# SCH_Plantcare_Module-v3_2024-10-22.net
KiCad netlist of a schematic drawn in EasyEDA
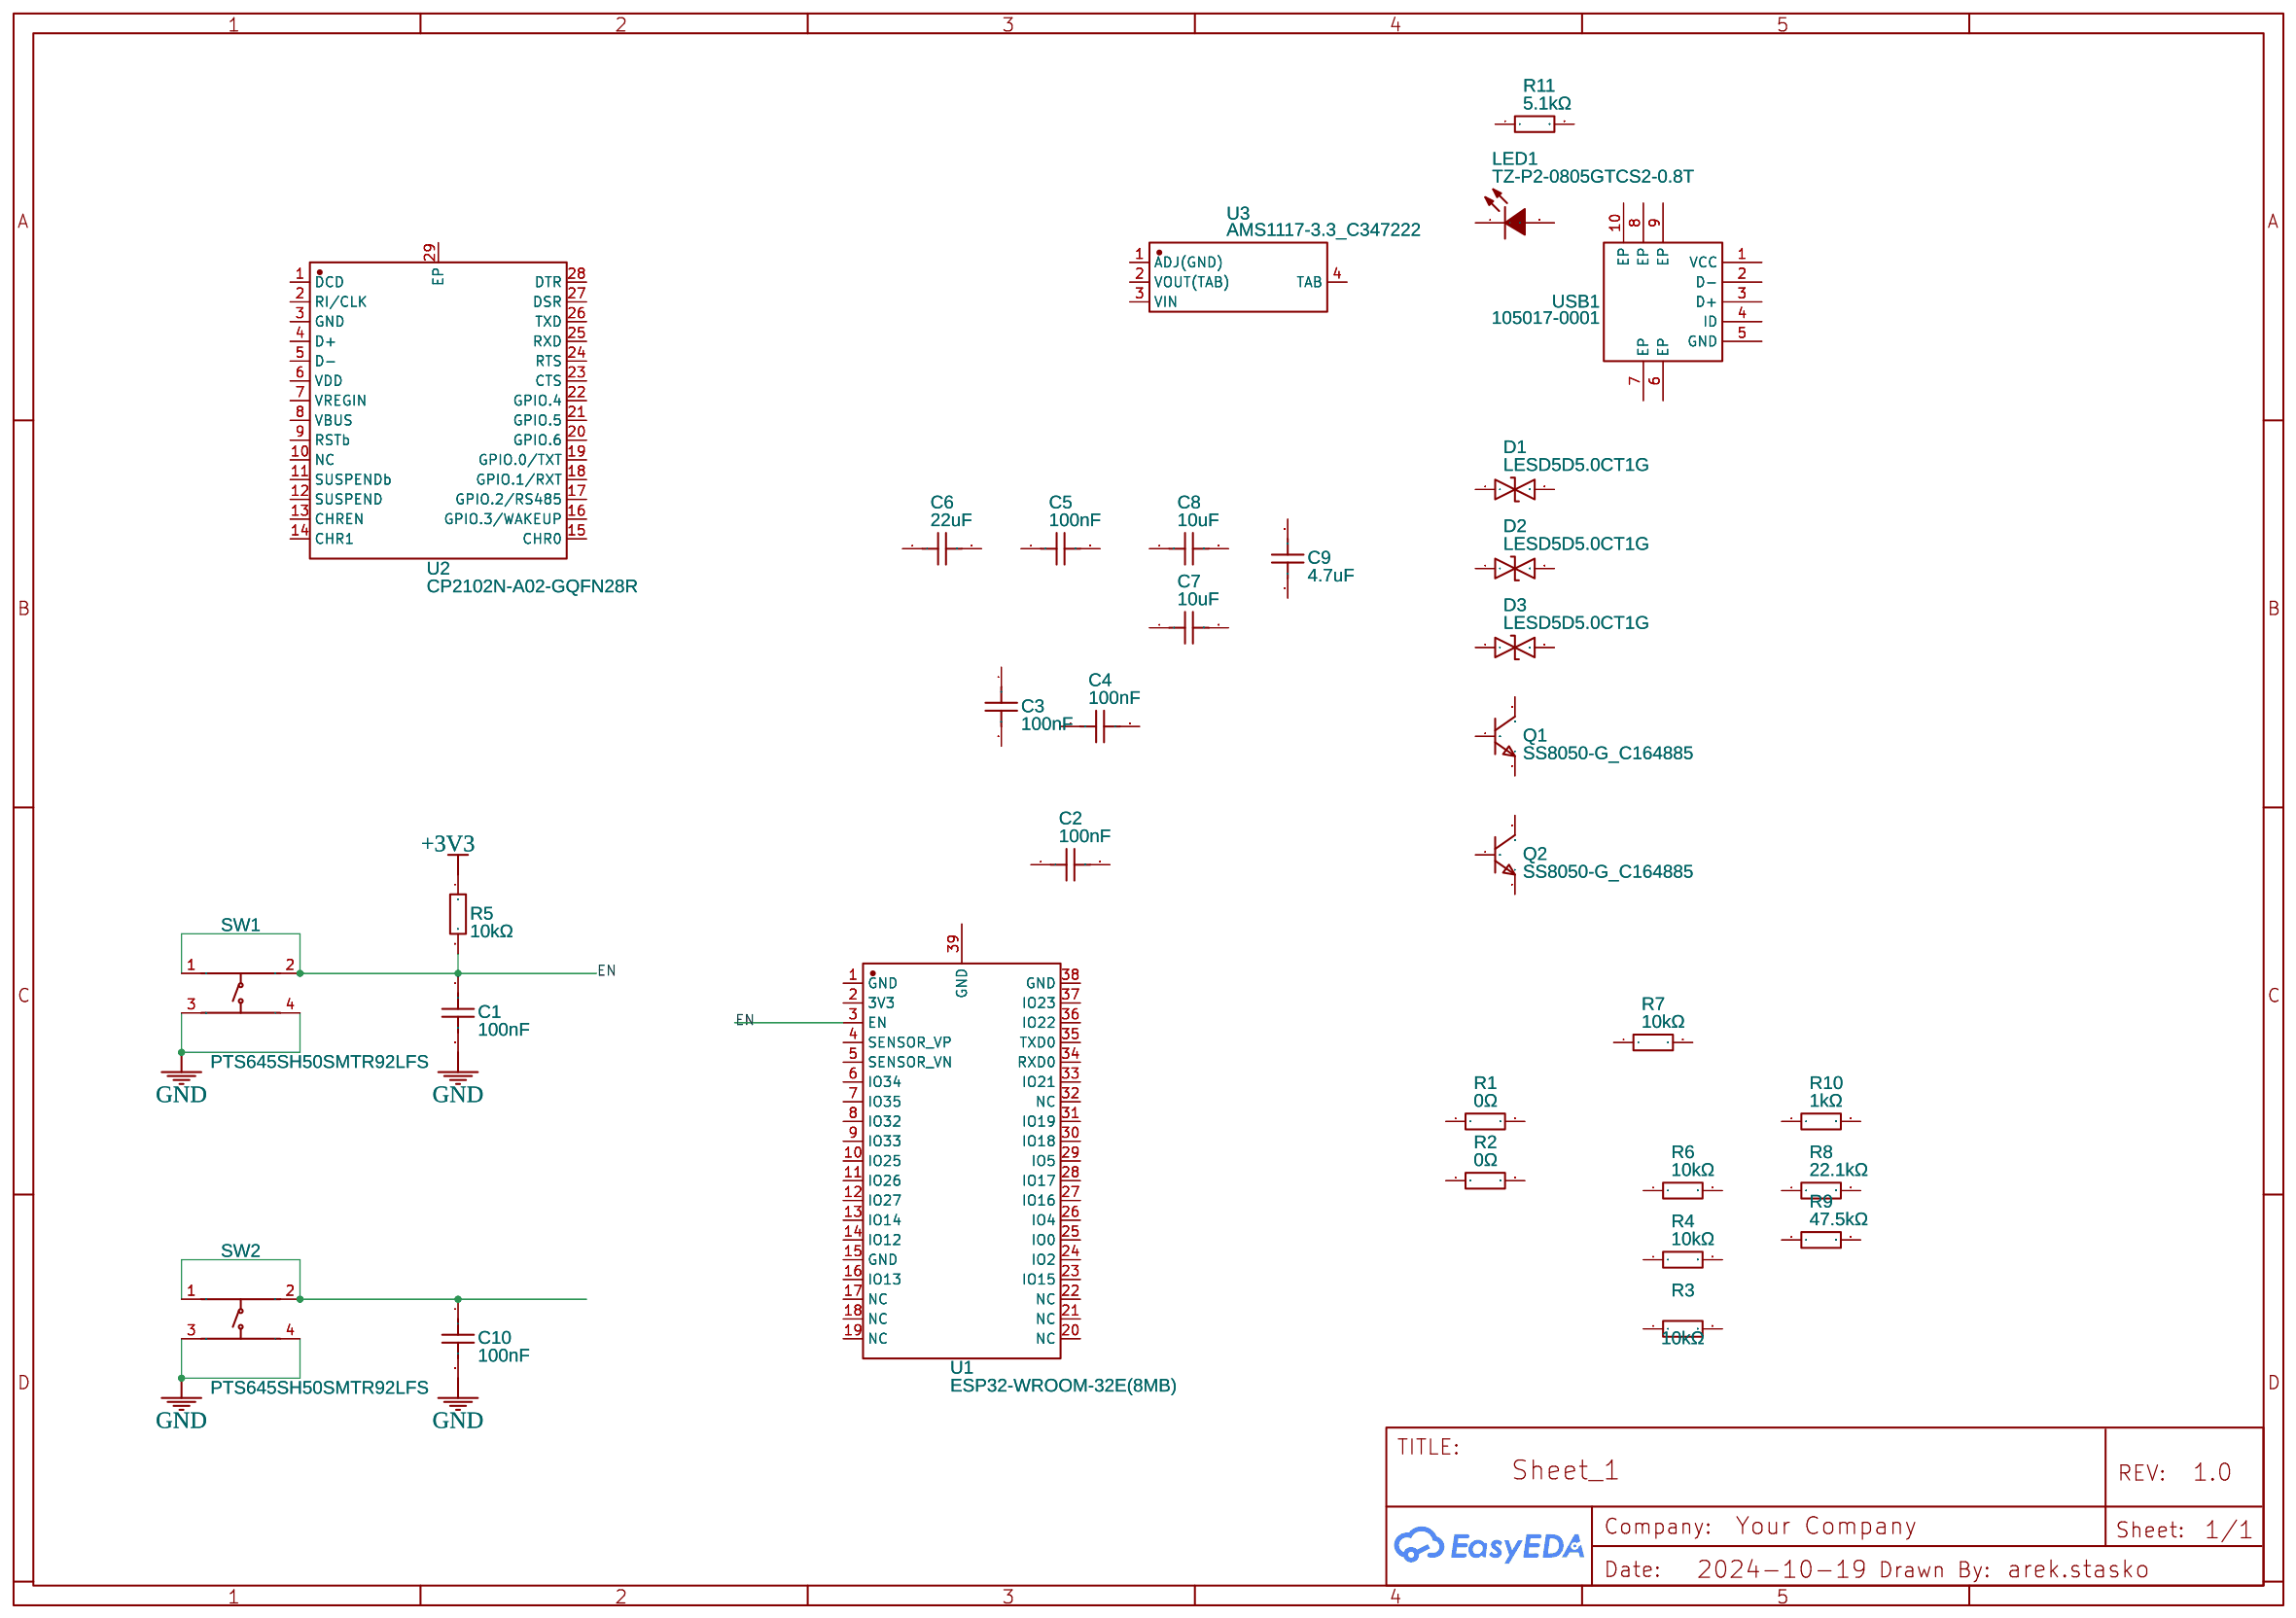
[diagram p0: schematic sheet]

(export (version "E")
  (design (tool "Eeschema 10.0.6"))
  (components
    (comp (ref "C1")
      (value "100nF")
      (fields
        (field (name "Manufacturer Part") "CL05B104KO5NNNC")
        (field (name "Manufacturer") "SAMSUNG(三星)")
      )
      (libsource (lib "") (part "CL05B104KO5NNNC_1"))
    )
    (comp (ref "C2")
      (value "100nF")
      (fields
        (field (name "Manufacturer Part") "CL05B104KO5NNNC")
        (field (name "Manufacturer") "SAMSUNG(三星)")
      )
      (libsource (lib "") (part "CL05B104KO5NNNC"))
    )
    (comp (ref "C3")
      (value "100nF")
      (fields
        (field (name "Manufacturer Part") "CL05B104KO5NNNC")
        (field (name "Manufacturer") "SAMSUNG(三星)")
      )
      (libsource (lib "") (part "CL05B104KO5NNNC_1"))
    )
    (comp (ref "C4")
      (value "100nF")
      (fields
        (field (name "Manufacturer Part") "CL05B104KO5NNNC")
        (field (name "Manufacturer") "SAMSUNG(三星)")
      )
      (libsource (lib "") (part "CL05B104KO5NNNC"))
    )
    (comp (ref "C5")
      (value "100nF")
      (fields
        (field (name "Manufacturer Part") "CL05B104KO5NNNC")
        (field (name "Manufacturer") "SAMSUNG(三星)")
      )
      (libsource (lib "") (part "CL05B104KO5NNNC"))
    )
    (comp (ref "C6")
      (value "22uF")
      (fields
        (field (name "Manufacturer Part") "CL21A226MAYNNNE")
        (field (name "Manufacturer") "SAMSUNG(三星)")
      )
      (libsource (lib "") (part "CL21A226MAYNNNE"))
    )
    (comp (ref "C7")
      (value "10uF")
      (fields
        (field (name "Manufacturer Part") "CL05A106MP5NUNC")
        (field (name "Manufacturer") "SAMSUNG(三星)")
      )
      (libsource (lib "") (part "CL05A106MP5NUNC_C315248"))
    )
    (comp (ref "C8")
      (value "10uF")
      (fields
        (field (name "Manufacturer Part") "CL05A106MP5NUNC")
        (field (name "Manufacturer") "SAMSUNG(三星)")
      )
      (libsource (lib "") (part "CL05A106MP5NUNC_C315248"))
    )
    (comp (ref "C9")
      (value "4.7uF")
      (fields
        (field (name "Manufacturer Part") "CL05A475KP5NRNC")
        (field (name "Manufacturer") "SAMSUNG(三星)")
      )
      (libsource (lib "") (part "CL05A475KP5NRNC"))
    )
    (comp (ref "C10")
      (value "100nF")
      (fields
        (field (name "Manufacturer Part") "CL05B104KO5NNNC")
        (field (name "Manufacturer") "SAMSUNG(三星)")
      )
      (libsource (lib "") (part "CL05B104KO5NNNC_1"))
    )
    (comp (ref "D1")
      (value "LESD5D5.0CT1G")
      (fields (field (name "Manufacturer") "LRC(乐山无线电)"))
      (libsource (lib "") (part "LESD5D5.0CT1G"))
    )
    (comp (ref "D2")
      (value "LESD5D5.0CT1G")
      (fields (field (name "Manufacturer") "LRC(乐山无线电)"))
      (libsource (lib "") (part "LESD5D5.0CT1G"))
    )
    (comp (ref "D3")
      (value "LESD5D5.0CT1G")
      (fields (field (name "Manufacturer") "LRC(乐山无线电)"))
      (libsource (lib "") (part "LESD5D5.0CT1G"))
    )
    (comp (ref "LED1")
      (value "TZ-P2-0805GTCS2-0.8T")
      (fields (field (name "Manufacturer") "TUOZHAN(拓展光电)"))
      (libsource (lib "") (part "TZ-P2-0805GTCS2-0.8T"))
    )
    (comp (ref "Q1")
      (value "SS8050-G_C164885")
      (fields (field (name "Manufacturer Part") "SS8050-G") (field (name "Manufacturer") "CJ(江苏长电/长晶)"))
      (libsource (lib "") (part "SS8050-G_C164885"))
    )
    (comp (ref "Q2")
      (value "SS8050-G_C164885")
      (fields (field (name "Manufacturer Part") "SS8050-G") (field (name "Manufacturer") "CJ(江苏长电/长晶)"))
      (libsource (lib "") (part "SS8050-G_C164885"))
    )
    (comp (ref "R1")
      (value "0Ω")
      (fields
        (field (name "Manufacturer Part") "0402WGF0000TCE")
        (field (name "Manufacturer") "UNI-ROYAL(厚声)")
      )
      (libsource (lib "") (part "0402WGF0000TCE"))
    )
    (comp (ref "R2")
      (value "0Ω")
      (fields
        (field (name "Manufacturer Part") "0402WGF0000TCE")
        (field (name "Manufacturer") "UNI-ROYAL(厚声)")
      )
      (libsource (lib "") (part "0402WGF0000TCE"))
    )
    (comp (ref "R3")
      (value "10kΩ")
      (fields
        (field (name "Manufacturer Part") "0402WGF1002TCE")
        (field (name "Manufacturer") "UNI-ROYAL(厚声)")
      )
      (libsource (lib "") (part "0402WGF1002TCE"))
    )
    (comp (ref "R4")
      (value "10kΩ")
      (fields
        (field (name "Manufacturer Part") "0402WGF1002TCE")
        (field (name "Manufacturer") "UNI-ROYAL(厚声)")
      )
      (libsource (lib "") (part "0402WGF1002TCE"))
    )
    (comp (ref "R5")
      (value "10kΩ")
      (fields
        (field (name "Manufacturer Part") "0402WGF1002TCE")
        (field (name "Manufacturer") "UNI-ROYAL(厚声)")
      )
      (libsource (lib "") (part "0402WGF1002TCE_1"))
    )
    (comp (ref "R6")
      (value "10kΩ")
      (fields
        (field (name "Manufacturer Part") "0402WGF1002TCE")
        (field (name "Manufacturer") "UNI-ROYAL(厚声)")
      )
      (libsource (lib "") (part "0402WGF1002TCE"))
    )
    (comp (ref "R7")
      (value "10kΩ")
      (fields
        (field (name "Manufacturer Part") "0402WGF1002TCE")
        (field (name "Manufacturer") "UNI-ROYAL(厚声)")
      )
      (libsource (lib "") (part "0402WGF1002TCE"))
    )
    (comp (ref "R8")
      (value "22.1kΩ")
      (fields
        (field (name "Manufacturer Part") "0402WGF2212TCE")
        (field (name "Manufacturer") "UNI-ROYAL(厚声)")
      )
      (libsource (lib "") (part "0402WGF2212TCE"))
    )
    (comp (ref "R9")
      (value "47.5kΩ")
      (fields
        (field (name "Manufacturer Part") "0402WGF4752TCE")
        (field (name "Manufacturer") "UNI-ROYAL(厚声)")
      )
      (libsource (lib "") (part "0402WGF4752TCE"))
    )
    (comp (ref "R10")
      (value "1kΩ")
      (fields
        (field (name "Manufacturer Part") "0402WGF1001TCE")
        (field (name "Manufacturer") "UNI-ROYAL(厚声)")
      )
      (libsource (lib "") (part "0402WGF1001TCE"))
    )
    (comp (ref "R11")
      (value "5.1kΩ")
      (fields
        (field (name "Manufacturer Part") "0402WGF5101TCE")
        (field (name "Manufacturer") "UNI-ROYAL(厚声)")
      )
      (libsource (lib "") (part "0402WGF5101TCE"))
    )
    (comp (ref "SW1")
      (value "PTS645SH50SMTR92LFS")
      (fields (field (name "Manufacturer") "C&K"))
      (libsource (lib "") (part "PTS645SH50SMTR92LFS"))
    )
    (comp (ref "SW2")
      (value "PTS645SH50SMTR92LFS")
      (fields (field (name "Manufacturer") "C&K"))
      (libsource (lib "") (part "PTS645SH50SMTR92LFS"))
    )
    (comp (ref "U1")
      (value "ESP32-WROOM-32E(8MB)")
      (fields
        (field (name "Manufacturer Part") "ESP32-WROOM-32E-N8")
        (field (name "Manufacturer") "ESPRESSIF(乐鑫)")
      )
      (libsource (lib "") (part "ESP32-WROOM-32E(8MB)"))
    )
    (comp (ref "U2")
      (value "CP2102N-A02-GQFN28R")
      (fields (field (name "Manufacturer") "SKYWORKS/SILICON LABS(芯科)"))
      (libsource (lib "") (part "CP2102N-A02-GQFN28R"))
    )
    (comp (ref "U3")
      (value "AMS1117-3.3_C347222")
      (fields (field (name "Manufacturer Part") "AMS1117-3.3") (field (name "Manufacturer") "UMW(友台半导体)"))
      (libsource (lib "") (part "AMS1117-3.3_C347222"))
    )
    (comp (ref "USB1")
      (value "105017-0001")
      (fields (field (name "Manufacturer Part") "1050170001") (field (name "Manufacturer") "MOLEX"))
      (libsource (lib "") (part "105017-0001"))
    )
  )
  (nets
    (net (code "1") (name "+3V3") (class "Default")
      (node (ref "R5") (pin "1") (pinfunction "1_1") (pintype "input"))
    )
    (net (code "2") (name "/EN") (class "Default")
      (node (ref "C1") (pin "1") (pinfunction "1_1") (pintype "unspecified"))
      (node (ref "R5") (pin "2") (pinfunction "2_2") (pintype "input"))
      (node (ref "SW1") (pin "1") (pinfunction "1_1") (pintype "unspecified"))
      (node (ref "SW1") (pin "2") (pinfunction "2_2") (pintype "unspecified"))
      (node (ref "U1") (pin "3") (pinfunction "EN_3") (pintype "unspecified"))
    )
    (net (code "3") (name "GND") (class "Default")
      (node (ref "C1") (pin "2") (pinfunction "2_2") (pintype "unspecified"))
      (node (ref "C10") (pin "2") (pinfunction "2_2") (pintype "unspecified"))
      (node (ref "SW1") (pin "3") (pinfunction "3_3") (pintype "unspecified"))
      (node (ref "SW1") (pin "4") (pinfunction "4_4") (pintype "unspecified"))
      (node (ref "SW2") (pin "3") (pinfunction "3_3") (pintype "unspecified"))
      (node (ref "SW2") (pin "4") (pinfunction "4_4") (pintype "unspecified"))
    )
    (net (code "4") (name "Net-(C10-Pad1)") (class "Default")
      (node (ref "C10") (pin "1") (pinfunction "1_1") (pintype "unspecified"))
      (node (ref "SW2") (pin "1") (pinfunction "1_1") (pintype "unspecified"))
      (node (ref "SW2") (pin "2") (pinfunction "2_2") (pintype "unspecified"))
    )
    (net (code "5") (name "unconnected-(C2-Pad1)") (class "Default")
      (node (ref "C2") (pin "1") (pinfunction "1_1") (pintype "unspecified"))
    )
    (net (code "6") (name "unconnected-(C2-Pad2)") (class "Default")
      (node (ref "C2") (pin "2") (pinfunction "2_2") (pintype "unspecified"))
    )
    (net (code "7") (name "unconnected-(C3-Pad1)") (class "Default")
      (node (ref "C3") (pin "1") (pinfunction "1_1") (pintype "unspecified"))
    )
    (net (code "8") (name "unconnected-(C3-Pad2)") (class "Default")
      (node (ref "C3") (pin "2") (pinfunction "2_2") (pintype "unspecified"))
    )
    (net (code "9") (name "unconnected-(C4-Pad1)") (class "Default")
      (node (ref "C4") (pin "1") (pinfunction "1_1") (pintype "unspecified"))
    )
    (net (code "10") (name "unconnected-(C4-Pad2)") (class "Default")
      (node (ref "C4") (pin "2") (pinfunction "2_2") (pintype "unspecified"))
    )
    (net (code "11") (name "unconnected-(C5-Pad1)") (class "Default")
      (node (ref "C5") (pin "1") (pinfunction "1_1") (pintype "unspecified"))
    )
    (net (code "12") (name "unconnected-(C5-Pad2)") (class "Default")
      (node (ref "C5") (pin "2") (pinfunction "2_2") (pintype "unspecified"))
    )
    (net (code "13") (name "unconnected-(C6-Pad1)") (class "Default")
      (node (ref "C6") (pin "1") (pinfunction "1_1") (pintype "unspecified"))
    )
    (net (code "14") (name "unconnected-(C6-Pad2)") (class "Default")
      (node (ref "C6") (pin "2") (pinfunction "2_2") (pintype "unspecified"))
    )
    (net (code "15") (name "unconnected-(C7-Pad1)") (class "Default")
      (node (ref "C7") (pin "1") (pinfunction "1_1") (pintype "unspecified"))
    )
    (net (code "16") (name "unconnected-(C7-Pad2)") (class "Default")
      (node (ref "C7") (pin "2") (pinfunction "2_2") (pintype "unspecified"))
    )
    (net (code "17") (name "unconnected-(C8-Pad1)") (class "Default")
      (node (ref "C8") (pin "1") (pinfunction "1_1") (pintype "unspecified"))
    )
    (net (code "18") (name "unconnected-(C8-Pad2)") (class "Default")
      (node (ref "C8") (pin "2") (pinfunction "2_2") (pintype "unspecified"))
    )
    (net (code "19") (name "unconnected-(C9-Pad1)") (class "Default")
      (node (ref "C9") (pin "1") (pinfunction "1_1") (pintype "unspecified"))
    )
    (net (code "20") (name "unconnected-(C9-Pad2)") (class "Default")
      (node (ref "C9") (pin "2") (pinfunction "2_2") (pintype "unspecified"))
    )
    (net (code "21") (name "unconnected-(D1-Pad1)") (class "Default")
      (node (ref "D1") (pin "1") (pinfunction "1_1") (pintype "unspecified"))
    )
    (net (code "22") (name "unconnected-(D1-Pad2)") (class "Default")
      (node (ref "D1") (pin "2") (pinfunction "2_2") (pintype "unspecified"))
    )
    (net (code "23") (name "unconnected-(D2-Pad1)") (class "Default")
      (node (ref "D2") (pin "1") (pinfunction "1_1") (pintype "unspecified"))
    )
    (net (code "24") (name "unconnected-(D2-Pad2)") (class "Default")
      (node (ref "D2") (pin "2") (pinfunction "2_2") (pintype "unspecified"))
    )
    (net (code "25") (name "unconnected-(D3-Pad1)") (class "Default")
      (node (ref "D3") (pin "1") (pinfunction "1_1") (pintype "unspecified"))
    )
    (net (code "26") (name "unconnected-(D3-Pad2)") (class "Default")
      (node (ref "D3") (pin "2") (pinfunction "2_2") (pintype "unspecified"))
    )
    (net (code "27") (name "unconnected-(LED1-+-Pad2)") (class "Default")
      (node (ref "LED1") (pin "2") (pinfunction "+_2") (pintype "unspecified"))
    )
    (net (code "28") (name "unconnected-(LED1---Pad1)") (class "Default")
      (node (ref "LED1") (pin "1") (pinfunction "-_1") (pintype "unspecified"))
    )
    (net (code "29") (name "unconnected-(Q1-B-Pad1)") (class "Default")
      (node (ref "Q1") (pin "1") (pinfunction "B_1") (pintype "unspecified"))
    )
    (net (code "30") (name "unconnected-(Q1-C-Pad3)") (class "Default")
      (node (ref "Q1") (pin "3") (pinfunction "C_3") (pintype "unspecified"))
    )
    (net (code "31") (name "unconnected-(Q1-E-Pad2)") (class "Default")
      (node (ref "Q1") (pin "2") (pinfunction "E_2") (pintype "unspecified"))
    )
    (net (code "32") (name "unconnected-(Q2-B-Pad1)") (class "Default")
      (node (ref "Q2") (pin "1") (pinfunction "B_1") (pintype "unspecified"))
    )
    (net (code "33") (name "unconnected-(Q2-C-Pad3)") (class "Default")
      (node (ref "Q2") (pin "3") (pinfunction "C_3") (pintype "unspecified"))
    )
    (net (code "34") (name "unconnected-(Q2-E-Pad2)") (class "Default")
      (node (ref "Q2") (pin "2") (pinfunction "E_2") (pintype "unspecified"))
    )
    (net (code "35") (name "unconnected-(R1-Pad1)") (class "Default")
      (node (ref "R1") (pin "1") (pinfunction "1_1") (pintype "input"))
    )
    (net (code "36") (name "unconnected-(R1-Pad2)") (class "Default")
      (node (ref "R1") (pin "2") (pinfunction "2_2") (pintype "input"))
    )
    (net (code "37") (name "unconnected-(R2-Pad1)") (class "Default")
      (node (ref "R2") (pin "1") (pinfunction "1_1") (pintype "input"))
    )
    (net (code "38") (name "unconnected-(R2-Pad2)") (class "Default")
      (node (ref "R2") (pin "2") (pinfunction "2_2") (pintype "input"))
    )
    (net (code "39") (name "unconnected-(R3-Pad1)") (class "Default")
      (node (ref "R3") (pin "1") (pinfunction "1_1") (pintype "input"))
    )
    (net (code "40") (name "unconnected-(R3-Pad2)") (class "Default")
      (node (ref "R3") (pin "2") (pinfunction "2_2") (pintype "input"))
    )
    (net (code "41") (name "unconnected-(R4-Pad1)") (class "Default")
      (node (ref "R4") (pin "1") (pinfunction "1_1") (pintype "input"))
    )
    (net (code "42") (name "unconnected-(R4-Pad2)") (class "Default")
      (node (ref "R4") (pin "2") (pinfunction "2_2") (pintype "input"))
    )
    (net (code "43") (name "unconnected-(R6-Pad1)") (class "Default")
      (node (ref "R6") (pin "1") (pinfunction "1_1") (pintype "input"))
    )
    (net (code "44") (name "unconnected-(R6-Pad2)") (class "Default")
      (node (ref "R6") (pin "2") (pinfunction "2_2") (pintype "input"))
    )
    (net (code "45") (name "unconnected-(R7-Pad1)") (class "Default")
      (node (ref "R7") (pin "1") (pinfunction "1_1") (pintype "input"))
    )
    (net (code "46") (name "unconnected-(R7-Pad2)") (class "Default")
      (node (ref "R7") (pin "2") (pinfunction "2_2") (pintype "input"))
    )
    (net (code "47") (name "unconnected-(R8-Pad1)") (class "Default")
      (node (ref "R8") (pin "1") (pinfunction "1_1") (pintype "input"))
    )
    (net (code "48") (name "unconnected-(R8-Pad2)") (class "Default")
      (node (ref "R8") (pin "2") (pinfunction "2_2") (pintype "input"))
    )
    (net (code "49") (name "unconnected-(R9-Pad1)") (class "Default")
      (node (ref "R9") (pin "1") (pinfunction "1_1") (pintype "input"))
    )
    (net (code "50") (name "unconnected-(R9-Pad2)") (class "Default")
      (node (ref "R9") (pin "2") (pinfunction "2_2") (pintype "input"))
    )
    (net (code "51") (name "unconnected-(R10-Pad1)") (class "Default")
      (node (ref "R10") (pin "1") (pinfunction "1_1") (pintype "input"))
    )
    (net (code "52") (name "unconnected-(R10-Pad2)") (class "Default")
      (node (ref "R10") (pin "2") (pinfunction "2_2") (pintype "input"))
    )
    (net (code "53") (name "unconnected-(R11-Pad1)") (class "Default")
      (node (ref "R11") (pin "1") (pinfunction "1_1") (pintype "input"))
    )
    (net (code "54") (name "unconnected-(R11-Pad2)") (class "Default")
      (node (ref "R11") (pin "2") (pinfunction "2_2") (pintype "input"))
    )
    (net (code "55") (name "unconnected-(U1-3V3-Pad2)") (class "Default")
      (node (ref "U1") (pin "2") (pinfunction "3V3_2") (pintype "unspecified"))
    )
    (net (code "56") (name "unconnected-(U1-GND-Pad1)") (class "Default")
      (node (ref "U1") (pin "1") (pinfunction "GND_1") (pintype "unspecified"))
    )
    (net (code "57") (name "unconnected-(U1-GND-Pad15)") (class "Default")
      (node (ref "U1") (pin "15") (pinfunction "GND_15") (pintype "unspecified"))
    )
    (net (code "58") (name "unconnected-(U1-GND-Pad38)") (class "Default")
      (node (ref "U1") (pin "38") (pinfunction "GND_38") (pintype "unspecified"))
    )
    (net (code "59") (name "unconnected-(U1-GND-Pad39)") (class "Default")
      (node (ref "U1") (pin "39") (pinfunction "GND_39") (pintype "unspecified"))
    )
    (net (code "60") (name "unconnected-(U1-IO0-Pad25)") (class "Default")
      (node (ref "U1") (pin "25") (pinfunction "IO0_25") (pintype "unspecified"))
    )
    (net (code "61") (name "unconnected-(U1-IO2-Pad24)") (class "Default")
      (node (ref "U1") (pin "24") (pinfunction "IO2_24") (pintype "unspecified"))
    )
    (net (code "62") (name "unconnected-(U1-IO4-Pad26)") (class "Default")
      (node (ref "U1") (pin "26") (pinfunction "IO4_26") (pintype "unspecified"))
    )
    (net (code "63") (name "unconnected-(U1-IO5-Pad29)") (class "Default")
      (node (ref "U1") (pin "29") (pinfunction "IO5_29") (pintype "unspecified"))
    )
    (net (code "64") (name "unconnected-(U1-IO12-Pad14)") (class "Default")
      (node (ref "U1") (pin "14") (pinfunction "IO12_14") (pintype "unspecified"))
    )
    (net (code "65") (name "unconnected-(U1-IO13-Pad16)") (class "Default")
      (node (ref "U1") (pin "16") (pinfunction "IO13_16") (pintype "unspecified"))
    )
    (net (code "66") (name "unconnected-(U1-IO14-Pad13)") (class "Default")
      (node (ref "U1") (pin "13") (pinfunction "IO14_13") (pintype "unspecified"))
    )
    (net (code "67") (name "unconnected-(U1-IO15-Pad23)") (class "Default")
      (node (ref "U1") (pin "23") (pinfunction "IO15_23") (pintype "unspecified"))
    )
    (net (code "68") (name "unconnected-(U1-IO16-Pad27)") (class "Default")
      (node (ref "U1") (pin "27") (pinfunction "IO16_27") (pintype "unspecified"))
    )
    (net (code "69") (name "unconnected-(U1-IO17-Pad28)") (class "Default")
      (node (ref "U1") (pin "28") (pinfunction "IO17_28") (pintype "unspecified"))
    )
    (net (code "70") (name "unconnected-(U1-IO18-Pad30)") (class "Default")
      (node (ref "U1") (pin "30") (pinfunction "IO18_30") (pintype "unspecified"))
    )
    (net (code "71") (name "unconnected-(U1-IO19-Pad31)") (class "Default")
      (node (ref "U1") (pin "31") (pinfunction "IO19_31") (pintype "unspecified"))
    )
    (net (code "72") (name "unconnected-(U1-IO21-Pad33)") (class "Default")
      (node (ref "U1") (pin "33") (pinfunction "IO21_33") (pintype "unspecified"))
    )
    (net (code "73") (name "unconnected-(U1-IO22-Pad36)") (class "Default")
      (node (ref "U1") (pin "36") (pinfunction "IO22_36") (pintype "unspecified"))
    )
    (net (code "74") (name "unconnected-(U1-IO23-Pad37)") (class "Default")
      (node (ref "U1") (pin "37") (pinfunction "IO23_37") (pintype "unspecified"))
    )
    (net (code "75") (name "unconnected-(U1-IO25-Pad10)") (class "Default")
      (node (ref "U1") (pin "10") (pinfunction "IO25_10") (pintype "unspecified"))
    )
    (net (code "76") (name "unconnected-(U1-IO26-Pad11)") (class "Default")
      (node (ref "U1") (pin "11") (pinfunction "IO26_11") (pintype "unspecified"))
    )
    (net (code "77") (name "unconnected-(U1-IO27-Pad12)") (class "Default")
      (node (ref "U1") (pin "12") (pinfunction "IO27_12") (pintype "unspecified"))
    )
    (net (code "78") (name "unconnected-(U1-IO32-Pad8)") (class "Default")
      (node (ref "U1") (pin "8") (pinfunction "IO32_8") (pintype "unspecified"))
    )
    (net (code "79") (name "unconnected-(U1-IO33-Pad9)") (class "Default")
      (node (ref "U1") (pin "9") (pinfunction "IO33_9") (pintype "unspecified"))
    )
    (net (code "80") (name "unconnected-(U1-IO34-Pad6)") (class "Default")
      (node (ref "U1") (pin "6") (pinfunction "IO34_6") (pintype "unspecified"))
    )
    (net (code "81") (name "unconnected-(U1-IO35-Pad7)") (class "Default")
      (node (ref "U1") (pin "7") (pinfunction "IO35_7") (pintype "unspecified"))
    )
    (net (code "82") (name "unconnected-(U1-NC-Pad17)") (class "Default")
      (node (ref "U1") (pin "17") (pinfunction "NC_17") (pintype "unspecified"))
    )
    (net (code "83") (name "unconnected-(U1-NC-Pad18)") (class "Default")
      (node (ref "U1") (pin "18") (pinfunction "NC_18") (pintype "unspecified"))
    )
    (net (code "84") (name "unconnected-(U1-NC-Pad19)") (class "Default")
      (node (ref "U1") (pin "19") (pinfunction "NC_19") (pintype "unspecified"))
    )
    (net (code "85") (name "unconnected-(U1-NC-Pad20)") (class "Default")
      (node (ref "U1") (pin "20") (pinfunction "NC_20") (pintype "unspecified"))
    )
    (net (code "86") (name "unconnected-(U1-NC-Pad21)") (class "Default")
      (node (ref "U1") (pin "21") (pinfunction "NC_21") (pintype "unspecified"))
    )
    (net (code "87") (name "unconnected-(U1-NC-Pad22)") (class "Default")
      (node (ref "U1") (pin "22") (pinfunction "NC_22") (pintype "unspecified"))
    )
    (net (code "88") (name "unconnected-(U1-NC-Pad32)") (class "Default")
      (node (ref "U1") (pin "32") (pinfunction "NC_32") (pintype "unspecified"))
    )
    (net (code "89") (name "unconnected-(U1-RXD0-Pad34)") (class "Default")
      (node (ref "U1") (pin "34") (pinfunction "RXD0_34") (pintype "unspecified"))
    )
    (net (code "90") (name "unconnected-(U1-SENSOR_VN-Pad5)") (class "Default")
      (node (ref "U1") (pin "5") (pinfunction "SENSOR_VN_5") (pintype "unspecified"))
    )
    (net (code "91") (name "unconnected-(U1-SENSOR_VP-Pad4)") (class "Default")
      (node (ref "U1") (pin "4") (pinfunction "SENSOR_VP_4") (pintype "unspecified"))
    )
    (net (code "92") (name "unconnected-(U1-TXD0-Pad35)") (class "Default")
      (node (ref "U1") (pin "35") (pinfunction "TXD0_35") (pintype "unspecified"))
    )
    (net (code "93") (name "unconnected-(U2-CHR0-Pad15)") (class "Default")
      (node (ref "U2") (pin "15") (pinfunction "CHR0_15") (pintype "unspecified"))
    )
    (net (code "94") (name "unconnected-(U2-CHR1-Pad14)") (class "Default")
      (node (ref "U2") (pin "14") (pinfunction "CHR1_14") (pintype "unspecified"))
    )
    (net (code "95") (name "unconnected-(U2-CHREN-Pad13)") (class "Default")
      (node (ref "U2") (pin "13") (pinfunction "CHREN_13") (pintype "unspecified"))
    )
    (net (code "96") (name "unconnected-(U2-CTS-Pad23)") (class "Default")
      (node (ref "U2") (pin "23") (pinfunction "CTS_23") (pintype "unspecified"))
    )
    (net (code "97") (name "unconnected-(U2-D+-Pad4)") (class "Default")
      (node (ref "U2") (pin "4") (pinfunction "D+_4") (pintype "unspecified"))
    )
    (net (code "98") (name "unconnected-(U2-D--Pad5)") (class "Default")
      (node (ref "U2") (pin "5") (pinfunction "D-_5") (pintype "unspecified"))
    )
    (net (code "99") (name "unconnected-(U2-DCD-Pad1)") (class "Default")
      (node (ref "U2") (pin "1") (pinfunction "DCD_1") (pintype "unspecified"))
    )
    (net (code "100") (name "unconnected-(U2-DSR-Pad27)") (class "Default")
      (node (ref "U2") (pin "27") (pinfunction "DSR_27") (pintype "unspecified"))
    )
    (net (code "101") (name "unconnected-(U2-DTR-Pad28)") (class "Default")
      (node (ref "U2") (pin "28") (pinfunction "DTR_28") (pintype "unspecified"))
    )
    (net (code "102") (name "unconnected-(U2-EP-Pad29)") (class "Default")
      (node (ref "U2") (pin "29") (pinfunction "EP_29") (pintype "unspecified"))
    )
    (net (code "103") (name "unconnected-(U2-GND-Pad3)") (class "Default")
      (node (ref "U2") (pin "3") (pinfunction "GND_3") (pintype "unspecified"))
    )
    (net (code "104") (name "unconnected-(U2-GPIO.0{slash}TXT-Pad19)") (class "Default")
      (node (ref "U2") (pin "19") (pinfunction "GPIO.0/TXT_19") (pintype "unspecified"))
    )
    (net (code "105") (name "unconnected-(U2-GPIO.1{slash}RXT-Pad18)") (class "Default")
      (node (ref "U2") (pin "18") (pinfunction "GPIO.1/RXT_18") (pintype "unspecified"))
    )
    (net (code "106") (name "unconnected-(U2-GPIO.2{slash}RS485-Pad17)") (class "Default")
      (node (ref "U2") (pin "17") (pinfunction "GPIO.2/RS485_17") (pintype "unspecified"))
    )
    (net (code "107") (name "unconnected-(U2-GPIO.3{slash}WAKEUP-Pad16)") (class "Default")
      (node (ref "U2") (pin "16") (pinfunction "GPIO.3/WAKEUP_16") (pintype "unspecified"))
    )
    (net (code "108") (name "unconnected-(U2-GPIO.4-Pad22)") (class "Default")
      (node (ref "U2") (pin "22") (pinfunction "GPIO.4_22") (pintype "unspecified"))
    )
    (net (code "109") (name "unconnected-(U2-GPIO.5-Pad21)") (class "Default")
      (node (ref "U2") (pin "21") (pinfunction "GPIO.5_21") (pintype "unspecified"))
    )
    (net (code "110") (name "unconnected-(U2-GPIO.6-Pad20)") (class "Default")
      (node (ref "U2") (pin "20") (pinfunction "GPIO.6_20") (pintype "unspecified"))
    )
    (net (code "111") (name "unconnected-(U2-NC-Pad10)") (class "Default")
      (node (ref "U2") (pin "10") (pinfunction "NC_10") (pintype "unspecified"))
    )
    (net (code "112") (name "unconnected-(U2-RI{slash}CLK-Pad2)") (class "Default")
      (node (ref "U2") (pin "2") (pinfunction "RI/CLK_2") (pintype "unspecified"))
    )
    (net (code "113") (name "unconnected-(U2-RSTb-Pad9)") (class "Default")
      (node (ref "U2") (pin "9") (pinfunction "RSTb_9") (pintype "unspecified"))
    )
    (net (code "114") (name "unconnected-(U2-RTS-Pad24)") (class "Default")
      (node (ref "U2") (pin "24") (pinfunction "RTS_24") (pintype "unspecified"))
    )
    (net (code "115") (name "unconnected-(U2-RXD-Pad25)") (class "Default")
      (node (ref "U2") (pin "25") (pinfunction "RXD_25") (pintype "unspecified"))
    )
    (net (code "116") (name "unconnected-(U2-SUSPEND-Pad12)") (class "Default")
      (node (ref "U2") (pin "12") (pinfunction "SUSPEND_12") (pintype "unspecified"))
    )
    (net (code "117") (name "unconnected-(U2-SUSPENDb-Pad11)") (class "Default")
      (node (ref "U2") (pin "11") (pinfunction "SUSPENDb_11") (pintype "unspecified"))
    )
    (net (code "118") (name "unconnected-(U2-TXD-Pad26)") (class "Default")
      (node (ref "U2") (pin "26") (pinfunction "TXD_26") (pintype "unspecified"))
    )
    (net (code "119") (name "unconnected-(U2-VBUS-Pad8)") (class "Default")
      (node (ref "U2") (pin "8") (pinfunction "VBUS_8") (pintype "unspecified"))
    )
    (net (code "120") (name "unconnected-(U2-VDD-Pad6)") (class "Default")
      (node (ref "U2") (pin "6") (pinfunction "VDD_6") (pintype "unspecified"))
    )
    (net (code "121") (name "unconnected-(U2-VREGIN-Pad7)") (class "Default")
      (node (ref "U2") (pin "7") (pinfunction "VREGIN_7") (pintype "unspecified"))
    )
    (net (code "122") (name "unconnected-(U3-ADJ(GND)-Pad1)") (class "Default")
      (node (ref "U3") (pin "1") (pinfunction "ADJ(GND)_1") (pintype "unspecified"))
    )
    (net (code "123") (name "unconnected-(U3-TAB-Pad4)") (class "Default")
      (node (ref "U3") (pin "4") (pinfunction "TAB_4") (pintype "unspecified"))
    )
    (net (code "124") (name "unconnected-(U3-VIN-Pad3)") (class "Default")
      (node (ref "U3") (pin "3") (pinfunction "VIN_3") (pintype "unspecified"))
    )
    (net (code "125") (name "unconnected-(U3-VOUT(TAB)-Pad2)") (class "Default")
      (node (ref "U3") (pin "2") (pinfunction "VOUT(TAB)_2") (pintype "unspecified"))
    )
    (net (code "126") (name "unconnected-(USB1-D+-Pad3)") (class "Default")
      (node (ref "USB1") (pin "3") (pinfunction "D+_3") (pintype "unspecified"))
    )
    (net (code "127") (name "unconnected-(USB1-D--Pad2)") (class "Default")
      (node (ref "USB1") (pin "2") (pinfunction "D-_2") (pintype "unspecified"))
    )
    (net (code "128") (name "unconnected-(USB1-EP-Pad6)") (class "Default")
      (node (ref "USB1") (pin "6") (pinfunction "EP_6") (pintype "unspecified"))
    )
    (net (code "129") (name "unconnected-(USB1-EP-Pad7)") (class "Default")
      (node (ref "USB1") (pin "7") (pinfunction "EP_7") (pintype "unspecified"))
    )
    (net (code "130") (name "unconnected-(USB1-EP-Pad8)") (class "Default")
      (node (ref "USB1") (pin "8") (pinfunction "EP_8") (pintype "unspecified"))
    )
    (net (code "131") (name "unconnected-(USB1-EP-Pad9)") (class "Default")
      (node (ref "USB1") (pin "9") (pinfunction "EP_9") (pintype "unspecified"))
    )
    (net (code "132") (name "unconnected-(USB1-EP-Pad10)") (class "Default")
      (node (ref "USB1") (pin "10") (pinfunction "EP_10") (pintype "unspecified"))
    )
    (net (code "133") (name "unconnected-(USB1-GND-Pad5)") (class "Default")
      (node (ref "USB1") (pin "5") (pinfunction "GND_5") (pintype "unspecified"))
    )
    (net (code "134") (name "unconnected-(USB1-ID-Pad4)") (class "Default")
      (node (ref "USB1") (pin "4") (pinfunction "ID_4") (pintype "unspecified"))
    )
    (net (code "135") (name "unconnected-(USB1-VCC-Pad1)") (class "Default")
      (node (ref "USB1") (pin "1") (pinfunction "VCC_1") (pintype "unspecified"))
    )
  )
)
